# Nano-Arduino-LoRa.net
KiCad netlist of a schematic drawn in Altium Designer
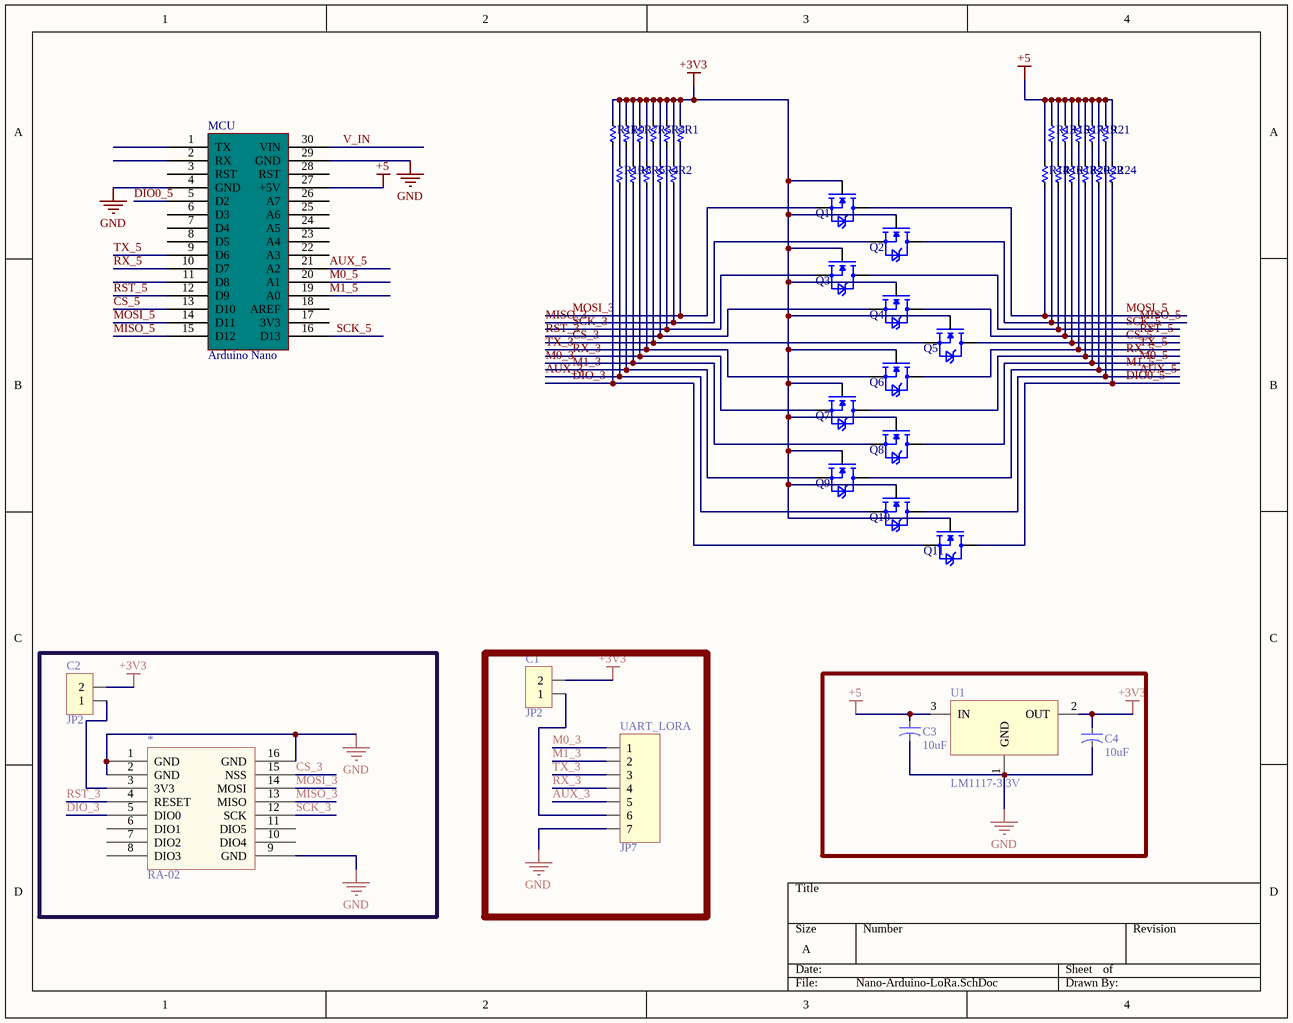
[diagram p0: Nano-Arduino-LoRa.SchDoc]

(export (version "E")
  (design (tool "Eeschema 10.0.6"))
  (components
    (comp (ref "*") (value "RA-02") (footprint "RA-02") (libsource (lib "RA-02") (part "RA-02")))
    (comp (ref "C1")
      (value "JP2")
      (footprint "JP2-C1T")
      (description "WR-PHD 2.54 mm Angled Socket Header")
      (fields
        (field (name "MANUFACTURER") "Würth Elektronik eiSos GmbH")
        (field (name "PARTNO") "613002143121")
        (field (name "CREATED BY") "Karrer Zheng")
      )
      (libsource (lib "LIBRARY") (part "JP2"))
    )
    (comp (ref "C2")
      (value "JP2")
      (footprint "JP2-C1T")
      (description "WR-PHD 2.54 mm Angled Socket Header")
      (fields
        (field (name "MANUFACTURER") "Würth Elektronik eiSos GmbH")
        (field (name "PARTNO") "613002143121")
        (field (name "CREATED BY") "Karrer Zheng")
      )
      (libsource (lib "LIBRARY") (part "JP2"))
    )
    (comp (ref "C3")
      (value "10uF")
      (footprint "CAP-ALU-SMD-4.5x5x1.4")
      (description "Polarized Capacitor (Axial)")
      (fields (field (name "PUBLISHER") "Altium Limited"))
      (libsource (lib "LIBRARY") (part "CN-ALU-SMD"))
    )
    (comp (ref "C4")
      (value "10uF")
      (footprint "CAP-ALU-SMD-4.5x5x1.4")
      (description "Polarized Capacitor (Axial)")
      (fields (field (name "PUBLISHER") "Altium Limited"))
      (libsource (lib "LIBRARY") (part "CN-ALU-SMD"))
    )
    (comp (ref "MCU")
      (value "Arduino Nano")
      (footprint "PCBComponent_1")
      (libsource (lib "Nano") (part "Component_1"))
    )
    (comp (ref "Q1")
      (value "BSS138")
      (footprint "SOT-23-3L")
      (description "FET SM NCH 50V 220mA SOT23-3L")
      (libsource (lib "electronpowered") (part "BSS138"))
    )
    (comp (ref "Q2")
      (value "BSS138")
      (footprint "SOT-23-3L")
      (description "FET SM NCH 50V 220mA SOT23-3L")
      (libsource (lib "electronpowered") (part "BSS138"))
    )
    (comp (ref "Q3")
      (value "BSS138")
      (footprint "SOT-23-3L")
      (description "FET SM NCH 50V 220mA SOT23-3L")
      (libsource (lib "electronpowered") (part "BSS138"))
    )
    (comp (ref "Q4")
      (value "BSS138")
      (footprint "SOT-23-3L")
      (description "FET SM NCH 50V 220mA SOT23-3L")
      (libsource (lib "electronpowered") (part "BSS138"))
    )
    (comp (ref "Q5")
      (value "BSS138")
      (footprint "SOT-23-3L")
      (description "FET SM NCH 50V 220mA SOT23-3L")
      (libsource (lib "electronpowered") (part "BSS138"))
    )
    (comp (ref "Q6")
      (value "BSS138")
      (footprint "SOT-23-3L")
      (description "FET SM NCH 50V 220mA SOT23-3L")
      (libsource (lib "electronpowered") (part "BSS138"))
    )
    (comp (ref "Q7")
      (value "BSS138")
      (footprint "SOT-23-3L")
      (description "FET SM NCH 50V 220mA SOT23-3L")
      (libsource (lib "electronpowered") (part "BSS138"))
    )
    (comp (ref "Q8")
      (value "BSS138")
      (footprint "SOT-23-3L")
      (description "FET SM NCH 50V 220mA SOT23-3L")
      (libsource (lib "electronpowered") (part "BSS138"))
    )
    (comp (ref "Q9")
      (value "BSS138")
      (footprint "SOT-23-3L")
      (description "FET SM NCH 50V 220mA SOT23-3L")
      (libsource (lib "electronpowered") (part "BSS138"))
    )
    (comp (ref "Q10")
      (value "BSS138")
      (footprint "SOT-23-3L")
      (description "FET SM NCH 50V 220mA SOT23-3L")
      (libsource (lib "electronpowered") (part "BSS138"))
    )
    (comp (ref "Q11")
      (value "BSS138")
      (footprint "SOT-23-3L")
      (description "FET SM NCH 50V 220mA SOT23-3L")
      (libsource (lib "electronpowered") (part "BSS138"))
    )
    (comp (ref "R1")
      (value "Res")
      (footprint "RES-SMD-0805")
      (description "Resistor")
      (fields
        (field (name "MANUFACTURER") "Generic Components")
        (field (name "PUBLISHER") "Altium Hobart Technology Centre")
      )
      (libsource (lib "LIBRARY") (part "Res-SMD"))
    )
    (comp (ref "R2")
      (value "Res")
      (footprint "RES-SMD-0805")
      (description "Resistor")
      (fields
        (field (name "MANUFACTURER") "Generic Components")
        (field (name "PUBLISHER") "Altium Hobart Technology Centre")
      )
      (libsource (lib "LIBRARY") (part "Res-SMD"))
    )
    (comp (ref "R3")
      (value "Res")
      (footprint "RES-SMD-0805")
      (description "Resistor")
      (fields
        (field (name "MANUFACTURER") "Generic Components")
        (field (name "PUBLISHER") "Altium Hobart Technology Centre")
      )
      (libsource (lib "LIBRARY") (part "Res-SMD"))
    )
    (comp (ref "R4")
      (value "Res")
      (footprint "RES-SMD-0805")
      (description "Resistor")
      (fields
        (field (name "MANUFACTURER") "Generic Components")
        (field (name "PUBLISHER") "Altium Hobart Technology Centre")
      )
      (libsource (lib "LIBRARY") (part "Res-SMD"))
    )
    (comp (ref "R5")
      (value "Res")
      (footprint "RES-SMD-0805")
      (description "Resistor")
      (fields
        (field (name "MANUFACTURER") "Generic Components")
        (field (name "PUBLISHER") "Altium Hobart Technology Centre")
      )
      (libsource (lib "LIBRARY") (part "Res-SMD"))
    )
    (comp (ref "R6")
      (value "Res")
      (footprint "RES-SMD-0805")
      (description "Resistor")
      (fields
        (field (name "MANUFACTURER") "Generic Components")
        (field (name "PUBLISHER") "Altium Hobart Technology Centre")
      )
      (libsource (lib "LIBRARY") (part "Res-SMD"))
    )
    (comp (ref "R7")
      (value "Res")
      (footprint "RES-SMD-0805")
      (description "Resistor")
      (fields
        (field (name "MANUFACTURER") "Generic Components")
        (field (name "PUBLISHER") "Altium Hobart Technology Centre")
      )
      (libsource (lib "LIBRARY") (part "Res-SMD"))
    )
    (comp (ref "R8")
      (value "Res")
      (footprint "RES-SMD-0805")
      (description "Resistor")
      (fields
        (field (name "MANUFACTURER") "Generic Components")
        (field (name "PUBLISHER") "Altium Hobart Technology Centre")
      )
      (libsource (lib "LIBRARY") (part "Res-SMD"))
    )
    (comp (ref "R9")
      (value "Res")
      (footprint "RES-SMD-0805")
      (description "Resistor")
      (fields
        (field (name "MANUFACTURER") "Generic Components")
        (field (name "PUBLISHER") "Altium Hobart Technology Centre")
      )
      (libsource (lib "LIBRARY") (part "Res-SMD"))
    )
    (comp (ref "R10")
      (value "Res")
      (footprint "RES-SMD-0805")
      (description "Resistor")
      (fields
        (field (name "MANUFACTURER") "Generic Components")
        (field (name "PUBLISHER") "Altium Hobart Technology Centre")
      )
      (libsource (lib "LIBRARY") (part "Res-SMD"))
    )
    (comp (ref "R11")
      (value "Res")
      (footprint "RES-SMD-0805")
      (description "Resistor")
      (fields
        (field (name "MANUFACTURER") "Generic Components")
        (field (name "PUBLISHER") "Altium Hobart Technology Centre")
      )
      (libsource (lib "LIBRARY") (part "Res-SMD"))
    )
    (comp (ref "R13")
      (value "Res")
      (footprint "RES-SMD-0805")
      (description "Resistor")
      (fields
        (field (name "MANUFACTURER") "Generic Components")
        (field (name "PUBLISHER") "Altium Hobart Technology Centre")
      )
      (libsource (lib "LIBRARY") (part "Res-SMD"))
    )
    (comp (ref "R14")
      (value "Res")
      (footprint "RES-SMD-0805")
      (description "Resistor")
      (fields
        (field (name "MANUFACTURER") "Generic Components")
        (field (name "PUBLISHER") "Altium Hobart Technology Centre")
      )
      (libsource (lib "LIBRARY") (part "Res-SMD"))
    )
    (comp (ref "R15")
      (value "Res")
      (footprint "RES-SMD-0805")
      (description "Resistor")
      (fields
        (field (name "MANUFACTURER") "Generic Components")
        (field (name "PUBLISHER") "Altium Hobart Technology Centre")
      )
      (libsource (lib "LIBRARY") (part "Res-SMD"))
    )
    (comp (ref "R16")
      (value "Res")
      (footprint "RES-SMD-0805")
      (description "Resistor")
      (fields
        (field (name "MANUFACTURER") "Generic Components")
        (field (name "PUBLISHER") "Altium Hobart Technology Centre")
      )
      (libsource (lib "LIBRARY") (part "Res-SMD"))
    )
    (comp (ref "R17")
      (value "Res")
      (footprint "RES-SMD-0805")
      (description "Resistor")
      (fields
        (field (name "MANUFACTURER") "Generic Components")
        (field (name "PUBLISHER") "Altium Hobart Technology Centre")
      )
      (libsource (lib "LIBRARY") (part "Res-SMD"))
    )
    (comp (ref "R18")
      (value "Res")
      (footprint "RES-SMD-0805")
      (description "Resistor")
      (fields
        (field (name "MANUFACTURER") "Generic Components")
        (field (name "PUBLISHER") "Altium Hobart Technology Centre")
      )
      (libsource (lib "LIBRARY") (part "Res-SMD"))
    )
    (comp (ref "R19")
      (value "Res")
      (footprint "RES-SMD-0805")
      (description "Resistor")
      (fields
        (field (name "MANUFACTURER") "Generic Components")
        (field (name "PUBLISHER") "Altium Hobart Technology Centre")
      )
      (libsource (lib "LIBRARY") (part "Res-SMD"))
    )
    (comp (ref "R20")
      (value "Res")
      (footprint "RES-SMD-0805")
      (description "Resistor")
      (fields
        (field (name "MANUFACTURER") "Generic Components")
        (field (name "PUBLISHER") "Altium Hobart Technology Centre")
      )
      (libsource (lib "LIBRARY") (part "Res-SMD"))
    )
    (comp (ref "R21")
      (value "Res")
      (footprint "RES-SMD-0805")
      (description "Resistor")
      (fields
        (field (name "MANUFACTURER") "Generic Components")
        (field (name "PUBLISHER") "Altium Hobart Technology Centre")
      )
      (libsource (lib "LIBRARY") (part "Res-SMD"))
    )
    (comp (ref "R22")
      (value "Res")
      (footprint "RES-SMD-0805")
      (description "Resistor")
      (fields
        (field (name "MANUFACTURER") "Generic Components")
        (field (name "PUBLISHER") "Altium Hobart Technology Centre")
      )
      (libsource (lib "LIBRARY") (part "Res-SMD"))
    )
    (comp (ref "R24")
      (value "Res")
      (footprint "RES-SMD-0805")
      (description "Resistor")
      (fields
        (field (name "MANUFACTURER") "Generic Components")
        (field (name "PUBLISHER") "Altium Hobart Technology Centre")
      )
      (libsource (lib "LIBRARY") (part "Res-SMD"))
    )
    (comp (ref "U1")
      (value "LM1117-3.3V")
      (footprint "SOT223")
      (description "800mA Low-Dropout Linear Regulator")
      (fields (field (name "CREATOR") "Nguyen Ba Bien"))
      (libsource (lib "LIBRARY") (part "LM1117"))
    )
    (comp (ref "UART_LORA")
      (value "JP7")
      (footprint "JP7-C1T")
      (description "WR-PHD 2.54 mm Angled Socket Header")
      (fields
        (field (name "MANUFACTURER") "Würth Elektronik eiSos GmbH")
        (field (name "PARTNO") "613007143121")
        (field (name "CREATED BY") "Karrer Zheng")
      )
      (libsource (lib "LIBRARY") (part "JP7"))
    )
  )
  (nets
    (net (code "1") (name "+3V3") (class "Default")
      (node (ref "C1") (pin "2") (pinfunction "2_2") (pintype "passive"))
      (node (ref "C2") (pin "2") (pinfunction "2_2") (pintype "passive"))
      (node (ref "C4") (pin "1") (pinfunction "1_1") (pintype "passive"))
      (node (ref "Q1") (pin "1") (pinfunction "1_1") (pintype "passive"))
      (node (ref "Q10") (pin "1") (pinfunction "1_1") (pintype "passive"))
      (node (ref "Q11") (pin "1") (pinfunction "1_1") (pintype "passive"))
      (node (ref "Q2") (pin "1") (pinfunction "1_1") (pintype "passive"))
      (node (ref "Q3") (pin "1") (pinfunction "1_1") (pintype "passive"))
      (node (ref "Q4") (pin "1") (pinfunction "1_1") (pintype "passive"))
      (node (ref "Q5") (pin "1") (pinfunction "1_1") (pintype "passive"))
      (node (ref "Q6") (pin "1") (pinfunction "1_1") (pintype "passive"))
      (node (ref "Q7") (pin "1") (pinfunction "1_1") (pintype "passive"))
      (node (ref "Q8") (pin "1") (pinfunction "1_1") (pintype "passive"))
      (node (ref "Q9") (pin "1") (pinfunction "1_1") (pintype "passive"))
      (node (ref "R1") (pin "1") (pinfunction "1_1") (pintype "passive"))
      (node (ref "R10") (pin "1") (pinfunction "1_1") (pintype "passive"))
      (node (ref "R11") (pin "1") (pinfunction "1_1") (pintype "passive"))
      (node (ref "R2") (pin "1") (pinfunction "1_1") (pintype "passive"))
      (node (ref "R3") (pin "1") (pinfunction "1_1") (pintype "passive"))
      (node (ref "R4") (pin "1") (pinfunction "1_1") (pintype "passive"))
      (node (ref "R5") (pin "1") (pinfunction "1_1") (pintype "passive"))
      (node (ref "R6") (pin "1") (pinfunction "1_1") (pintype "passive"))
      (node (ref "R7") (pin "1") (pinfunction "1_1") (pintype "passive"))
      (node (ref "R8") (pin "1") (pinfunction "1_1") (pintype "passive"))
      (node (ref "R9") (pin "1") (pinfunction "1_1") (pintype "passive"))
      (node (ref "U1") (pin "2") (pinfunction "OUT_2") (pintype "passive"))
    )
    (net (code "2") (name "+5") (class "Default")
      (node (ref "C3") (pin "1") (pinfunction "1_1") (pintype "passive"))
      (node (ref "MCU") (pin "27") (pinfunction "+5V_27") (pintype "passive"))
      (node (ref "R13") (pin "1") (pinfunction "1_1") (pintype "passive"))
      (node (ref "R14") (pin "1") (pinfunction "1_1") (pintype "passive"))
      (node (ref "R15") (pin "1") (pinfunction "1_1") (pintype "passive"))
      (node (ref "R16") (pin "1") (pinfunction "1_1") (pintype "passive"))
      (node (ref "R17") (pin "1") (pinfunction "1_1") (pintype "passive"))
      (node (ref "R18") (pin "1") (pinfunction "1_1") (pintype "passive"))
      (node (ref "R19") (pin "1") (pinfunction "1_1") (pintype "passive"))
      (node (ref "R20") (pin "1") (pinfunction "1_1") (pintype "passive"))
      (node (ref "R21") (pin "1") (pinfunction "1_1") (pintype "passive"))
      (node (ref "R22") (pin "1") (pinfunction "1_1") (pintype "passive"))
      (node (ref "R24") (pin "1") (pinfunction "1_1") (pintype "passive"))
      (node (ref "U1") (pin "3") (pinfunction "IN_3") (pintype "passive"))
    )
    (net (code "3") (name "/AUX_3") (class "Default")
      (node (ref "Q10") (pin "2") (pinfunction "2_2") (pintype "passive"))
      (node (ref "R10") (pin "2") (pinfunction "2_2") (pintype "passive"))
      (node (ref "UART_LORA") (pin "5") (pinfunction "5_5") (pintype "passive"))
    )
    (net (code "4") (name "/AUX_5") (class "Default")
      (node (ref "MCU") (pin "21") (pinfunction "A2_21") (pintype "passive"))
      (node (ref "Q10") (pin "3") (pinfunction "3_3") (pintype "passive"))
      (node (ref "R21") (pin "2") (pinfunction "2_2") (pintype "passive"))
    )
    (net (code "5") (name "/CS_3") (class "Default")
      (node (ref "*") (pin "15") (pinfunction "NSS_15") (pintype "passive"))
      (node (ref "Q5") (pin "2") (pinfunction "2_2") (pintype "passive"))
      (node (ref "R5") (pin "2") (pinfunction "2_2") (pintype "passive"))
    )
    (net (code "6") (name "/CS_5") (class "Default")
      (node (ref "MCU") (pin "13") (pinfunction "D10_13") (pintype "passive"))
      (node (ref "Q5") (pin "3") (pinfunction "3_3") (pintype "passive"))
      (node (ref "R18") (pin "2") (pinfunction "2_2") (pintype "passive"))
    )
    (net (code "7") (name "/DIO0_5") (class "Default")
      (node (ref "MCU") (pin "5") (pinfunction "D2_5") (pintype "passive"))
      (node (ref "Q11") (pin "3") (pinfunction "3_3") (pintype "passive"))
      (node (ref "R24") (pin "2") (pinfunction "2_2") (pintype "passive"))
    )
    (net (code "8") (name "/DIO_3") (class "Default")
      (node (ref "*") (pin "5") (pinfunction "DIO0_5") (pintype "passive"))
      (node (ref "Q11") (pin "2") (pinfunction "2_2") (pintype "passive"))
      (node (ref "R11") (pin "2") (pinfunction "2_2") (pintype "passive"))
    )
    (net (code "9") (name "/M0_3") (class "Default")
      (node (ref "Q8") (pin "2") (pinfunction "2_2") (pintype "passive"))
      (node (ref "R8") (pin "2") (pinfunction "2_2") (pintype "passive"))
      (node (ref "UART_LORA") (pin "1") (pinfunction "1_1") (pintype "passive"))
    )
    (net (code "10") (name "/M0_5") (class "Default")
      (node (ref "MCU") (pin "20") (pinfunction "A1_20") (pintype "passive"))
      (node (ref "Q8") (pin "3") (pinfunction "3_3") (pintype "passive"))
      (node (ref "R19") (pin "2") (pinfunction "2_2") (pintype "passive"))
    )
    (net (code "11") (name "/M1_3") (class "Default")
      (node (ref "Q9") (pin "2") (pinfunction "2_2") (pintype "passive"))
      (node (ref "R9") (pin "2") (pinfunction "2_2") (pintype "passive"))
      (node (ref "UART_LORA") (pin "2") (pinfunction "2_2") (pintype "passive"))
    )
    (net (code "12") (name "/M1_5") (class "Default")
      (node (ref "MCU") (pin "19") (pinfunction "A0_19") (pintype "passive"))
      (node (ref "Q9") (pin "3") (pinfunction "3_3") (pintype "passive"))
      (node (ref "R22") (pin "2") (pinfunction "2_2") (pintype "passive"))
    )
    (net (code "13") (name "/MISO_3") (class "Default")
      (node (ref "*") (pin "13") (pinfunction "MISO_13") (pintype "passive"))
      (node (ref "Q2") (pin "2") (pinfunction "2_2") (pintype "passive"))
      (node (ref "R2") (pin "2") (pinfunction "2_2") (pintype "passive"))
    )
    (net (code "14") (name "/MISO_5") (class "Default")
      (node (ref "MCU") (pin "15") (pinfunction "D12_15") (pintype "passive"))
      (node (ref "Q2") (pin "3") (pinfunction "3_3") (pintype "passive"))
      (node (ref "R13") (pin "2") (pinfunction "2_2") (pintype "passive"))
    )
    (net (code "15") (name "/MOSI_3") (class "Default")
      (node (ref "*") (pin "14") (pinfunction "MOSI_14") (pintype "passive"))
      (node (ref "Q1") (pin "2") (pinfunction "2_2") (pintype "passive"))
      (node (ref "R1") (pin "2") (pinfunction "2_2") (pintype "passive"))
    )
    (net (code "16") (name "/MOSI_5") (class "Default")
      (node (ref "MCU") (pin "14") (pinfunction "D11_14") (pintype "passive"))
      (node (ref "Q1") (pin "3") (pinfunction "3_3") (pintype "passive"))
      (node (ref "R14") (pin "2") (pinfunction "2_2") (pintype "passive"))
    )
    (net (code "17") (name "/RST_3") (class "Default")
      (node (ref "*") (pin "4") (pinfunction "RESET_4") (pintype "passive"))
      (node (ref "Q4") (pin "2") (pinfunction "2_2") (pintype "passive"))
      (node (ref "R4") (pin "2") (pinfunction "2_2") (pintype "passive"))
    )
    (net (code "18") (name "/RST_5") (class "Default")
      (node (ref "MCU") (pin "12") (pinfunction "D9_12") (pintype "passive"))
      (node (ref "Q4") (pin "3") (pinfunction "3_3") (pintype "passive"))
      (node (ref "R15") (pin "2") (pinfunction "2_2") (pintype "passive"))
    )
    (net (code "19") (name "/RX_3") (class "Default")
      (node (ref "Q7") (pin "2") (pinfunction "2_2") (pintype "passive"))
      (node (ref "R7") (pin "2") (pinfunction "2_2") (pintype "passive"))
      (node (ref "UART_LORA") (pin "4") (pinfunction "4_4") (pintype "passive"))
    )
    (net (code "20") (name "/RX_5") (class "Default")
      (node (ref "MCU") (pin "10") (pinfunction "D7_10") (pintype "passive"))
      (node (ref "Q7") (pin "3") (pinfunction "3_3") (pintype "passive"))
      (node (ref "R20") (pin "2") (pinfunction "2_2") (pintype "passive"))
    )
    (net (code "21") (name "/SCK_3") (class "Default")
      (node (ref "*") (pin "12") (pinfunction "SCK_12") (pintype "passive"))
      (node (ref "Q3") (pin "2") (pinfunction "2_2") (pintype "passive"))
      (node (ref "R3") (pin "2") (pinfunction "2_2") (pintype "passive"))
    )
    (net (code "22") (name "/SCK_5") (class "Default")
      (node (ref "MCU") (pin "16") (pinfunction "D13_16") (pintype "passive"))
      (node (ref "Q3") (pin "3") (pinfunction "3_3") (pintype "passive"))
      (node (ref "R16") (pin "2") (pinfunction "2_2") (pintype "passive"))
    )
    (net (code "23") (name "/TX_3") (class "Default")
      (node (ref "Q6") (pin "2") (pinfunction "2_2") (pintype "passive"))
      (node (ref "R6") (pin "2") (pinfunction "2_2") (pintype "passive"))
      (node (ref "UART_LORA") (pin "3") (pinfunction "3_3") (pintype "passive"))
    )
    (net (code "24") (name "/TX_5") (class "Default")
      (node (ref "MCU") (pin "9") (pinfunction "D6_9") (pintype "passive"))
      (node (ref "Q6") (pin "3") (pinfunction "3_3") (pintype "passive"))
      (node (ref "R17") (pin "2") (pinfunction "2_2") (pintype "passive"))
    )
    (net (code "25") (name "/V_IN") (class "Default")
      (node (ref "MCU") (pin "30") (pinfunction "VIN_30") (pintype "passive"))
    )
    (net (code "26") (name "GND") (class "Default")
      (node (ref "*") (pin "1") (pinfunction "GND_1") (pintype "passive"))
      (node (ref "*") (pin "16") (pinfunction "GND_16") (pintype "passive"))
      (node (ref "*") (pin "2") (pinfunction "GND_2") (pintype "passive"))
      (node (ref "*") (pin "9") (pinfunction "GND_9") (pintype "passive"))
      (node (ref "C3") (pin "2") (pinfunction "2_2") (pintype "passive"))
      (node (ref "C4") (pin "2") (pinfunction "2_2") (pintype "passive"))
      (node (ref "MCU") (pin "29") (pinfunction "GND_29") (pintype "passive"))
      (node (ref "MCU") (pin "4") (pinfunction "GND_4") (pintype "passive"))
      (node (ref "U1") (pin "1") (pinfunction "GND_1") (pintype "passive"))
      (node (ref "UART_LORA") (pin "7") (pinfunction "7_7") (pintype "passive"))
    )
    (net (code "27") (name "Net-(*-3V3)") (class "Default")
      (node (ref "*") (pin "3") (pinfunction "3V3_3") (pintype "passive"))
      (node (ref "C2") (pin "1") (pinfunction "1_1") (pintype "passive"))
    )
    (net (code "28") (name "Net-(C1-Pad1)") (class "Default")
      (node (ref "C1") (pin "1") (pinfunction "1_1") (pintype "passive"))
      (node (ref "UART_LORA") (pin "6") (pinfunction "6_6") (pintype "passive"))
    )
    (net (code "29") (name "unconnected-(*-DIO1-Pad6)") (class "Default")
      (node (ref "*") (pin "6") (pinfunction "DIO1_6") (pintype "passive"))
    )
    (net (code "30") (name "unconnected-(*-DIO2-Pad7)") (class "Default")
      (node (ref "*") (pin "7") (pinfunction "DIO2_7") (pintype "passive"))
    )
    (net (code "31") (name "unconnected-(*-DIO3-Pad8)") (class "Default")
      (node (ref "*") (pin "8") (pinfunction "DIO3_8") (pintype "passive"))
    )
    (net (code "32") (name "unconnected-(*-DIO4-Pad10)") (class "Default")
      (node (ref "*") (pin "10") (pinfunction "DIO4_10") (pintype "passive"))
    )
    (net (code "33") (name "unconnected-(*-DIO5-Pad11)") (class "Default")
      (node (ref "*") (pin "11") (pinfunction "DIO5_11") (pintype "passive"))
    )
    (net (code "34") (name "unconnected-(MCU-3V3-Pad17)") (class "Default")
      (node (ref "MCU") (pin "17") (pinfunction "3V3_17") (pintype "passive"))
    )
    (net (code "35") (name "unconnected-(MCU-A3-Pad22)") (class "Default")
      (node (ref "MCU") (pin "22") (pinfunction "A3_22") (pintype "passive"))
    )
    (net (code "36") (name "unconnected-(MCU-A4-Pad23)") (class "Default")
      (node (ref "MCU") (pin "23") (pinfunction "A4_23") (pintype "passive"))
    )
    (net (code "37") (name "unconnected-(MCU-A5-Pad24)") (class "Default")
      (node (ref "MCU") (pin "24") (pinfunction "A5_24") (pintype "passive"))
    )
    (net (code "38") (name "unconnected-(MCU-A6-Pad25)") (class "Default")
      (node (ref "MCU") (pin "25") (pinfunction "A6_25") (pintype "passive"))
    )
    (net (code "39") (name "unconnected-(MCU-A7-Pad26)") (class "Default")
      (node (ref "MCU") (pin "26") (pinfunction "A7_26") (pintype "passive"))
    )
    (net (code "40") (name "unconnected-(MCU-AREF-Pad18)") (class "Default")
      (node (ref "MCU") (pin "18") (pinfunction "AREF_18") (pintype "passive"))
    )
    (net (code "41") (name "unconnected-(MCU-D3-Pad6)") (class "Default")
      (node (ref "MCU") (pin "6") (pinfunction "D3_6") (pintype "passive"))
    )
    (net (code "42") (name "unconnected-(MCU-D4-Pad7)") (class "Default")
      (node (ref "MCU") (pin "7") (pinfunction "D4_7") (pintype "passive"))
    )
    (net (code "43") (name "unconnected-(MCU-D5-Pad8)") (class "Default")
      (node (ref "MCU") (pin "8") (pinfunction "D5_8") (pintype "passive"))
    )
    (net (code "44") (name "unconnected-(MCU-D8-Pad11)") (class "Default")
      (node (ref "MCU") (pin "11") (pinfunction "D8_11") (pintype "passive"))
    )
    (net (code "45") (name "unconnected-(MCU-RST-Pad3)") (class "Default")
      (node (ref "MCU") (pin "3") (pinfunction "RST_3") (pintype "passive"))
    )
    (net (code "46") (name "unconnected-(MCU-RST-Pad28)") (class "Default")
      (node (ref "MCU") (pin "28") (pinfunction "RST_28") (pintype "passive"))
    )
    (net (code "47") (name "unconnected-(MCU-RX-Pad2)") (class "Default")
      (node (ref "MCU") (pin "2") (pinfunction "RX_2") (pintype "passive"))
    )
    (net (code "48") (name "unconnected-(MCU-TX-Pad1)") (class "Default")
      (node (ref "MCU") (pin "1") (pinfunction "TX_1") (pintype "passive"))
    )
  )
)
